# bitchess.net
KiCad netlist of a schematic drawn in EAGLE
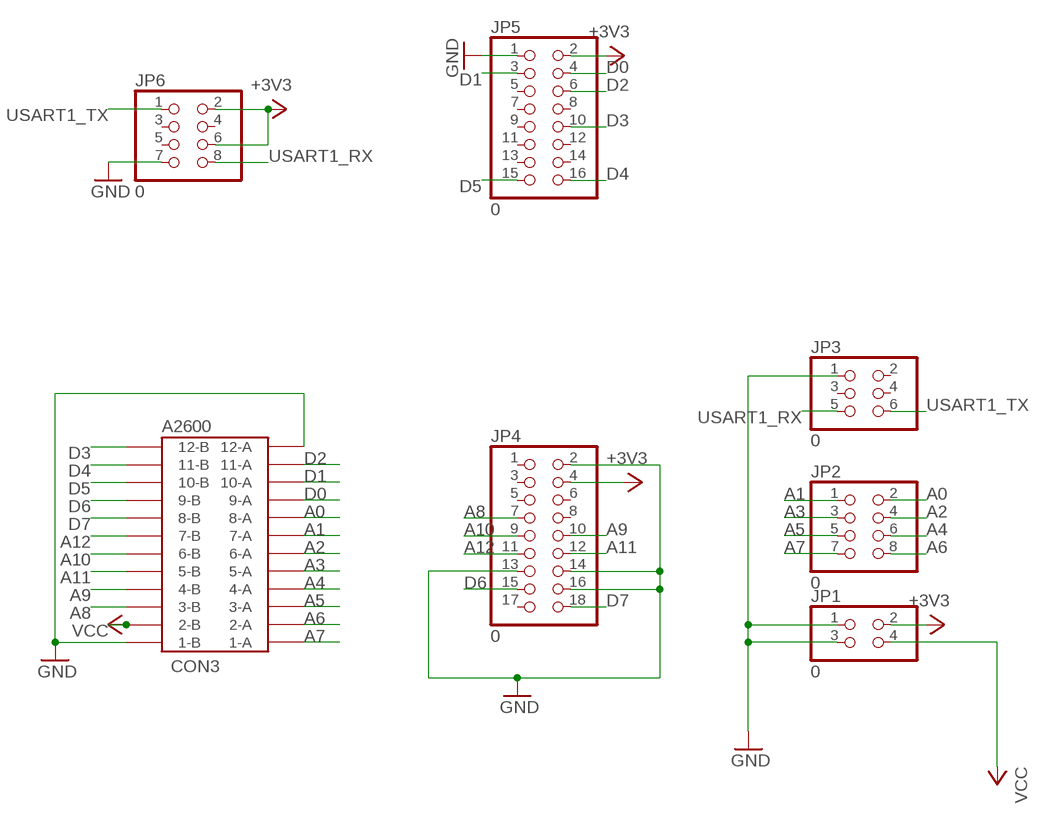
[diagram p0: schematic, sheet 1]

(export (version "E")
  (design (tool "Eeschema 10.0.6"))
  (components
    (comp (ref "CON3")
      (value "A2600")
      (footprint "eagle-import:24PINEDGE-254MM")
      (libsource (lib "eagle-import") (part "24PINEDGE-254MM"))
    )
    (comp (ref "JP1")
      (value "0")
      (footprint "eagle-import:2X02")
      (libsource (lib "eagle-import") (part "PINHD-2X2"))
    )
    (comp (ref "JP2")
      (value "0")
      (footprint "eagle-import:2X04")
      (libsource (lib "eagle-import") (part "PINHD-2X4"))
    )
    (comp (ref "JP3")
      (value "0")
      (footprint "eagle-import:2X03")
      (libsource (lib "eagle-import") (part "PINHD-2X3"))
    )
    (comp (ref "JP4")
      (value "0")
      (footprint "eagle-import:2X09")
      (libsource (lib "eagle-import") (part "PINHD-2X9"))
    )
    (comp (ref "JP5")
      (value "0")
      (footprint "eagle-import:2X08")
      (libsource (lib "eagle-import") (part "PINHD-2X8"))
    )
    (comp (ref "JP6")
      (value "0")
      (footprint "eagle-import:2X04")
      (libsource (lib "eagle-import") (part "PINHD-2X4"))
    )
  )
  (nets
    (net (code "1") (name "+3V3") (class "Default")
      (node (ref "JP1") (pin "2") (pinfunction "2_2") (pintype "passive"))
      (node (ref "JP4") (pin "4") (pinfunction "4_4") (pintype "passive"))
      (node (ref "JP5") (pin "2") (pinfunction "2_2") (pintype "passive"))
      (node (ref "JP6") (pin "2") (pinfunction "2_2") (pintype "passive"))
      (node (ref "JP6") (pin "6") (pinfunction "6_6") (pintype "passive"))
    )
    (net (code "2") (name "/A0") (class "Default")
      (node (ref "CON3") (pin "8-A") (pinfunction "8-A_8-A") (pintype "passive"))
      (node (ref "JP2") (pin "2") (pinfunction "2_2") (pintype "passive"))
    )
    (net (code "3") (name "/A1") (class "Default")
      (node (ref "CON3") (pin "7-A") (pinfunction "7-A_7-A") (pintype "passive"))
      (node (ref "JP2") (pin "1") (pinfunction "1_1") (pintype "passive"))
    )
    (net (code "4") (name "/A2") (class "Default")
      (node (ref "CON3") (pin "6-A") (pinfunction "6-A_6-A") (pintype "passive"))
      (node (ref "JP2") (pin "4") (pinfunction "4_4") (pintype "passive"))
    )
    (net (code "5") (name "/A3") (class "Default")
      (node (ref "CON3") (pin "5-A") (pinfunction "5-A_5-A") (pintype "passive"))
      (node (ref "JP2") (pin "3") (pinfunction "3_3") (pintype "passive"))
    )
    (net (code "6") (name "/A4") (class "Default")
      (node (ref "CON3") (pin "4-A") (pinfunction "4-A_4-A") (pintype "passive"))
      (node (ref "JP2") (pin "6") (pinfunction "6_6") (pintype "passive"))
    )
    (net (code "7") (name "/A5") (class "Default")
      (node (ref "CON3") (pin "3-A") (pinfunction "3-A_3-A") (pintype "passive"))
      (node (ref "JP2") (pin "5") (pinfunction "5_5") (pintype "passive"))
    )
    (net (code "8") (name "/A6") (class "Default")
      (node (ref "CON3") (pin "2-A") (pinfunction "2-A_2-A") (pintype "passive"))
      (node (ref "JP2") (pin "8") (pinfunction "8_8") (pintype "passive"))
    )
    (net (code "9") (name "/A7") (class "Default")
      (node (ref "CON3") (pin "1-A") (pinfunction "1-A_1-A") (pintype "passive"))
      (node (ref "JP2") (pin "7") (pinfunction "7_7") (pintype "passive"))
    )
    (net (code "10") (name "/A8") (class "Default")
      (node (ref "CON3") (pin "3-B") (pinfunction "3-B_3-B") (pintype "passive"))
      (node (ref "JP4") (pin "7") (pinfunction "7_7") (pintype "passive"))
    )
    (net (code "11") (name "/A9") (class "Default")
      (node (ref "CON3") (pin "4-B") (pinfunction "4-B_4-B") (pintype "passive"))
      (node (ref "JP4") (pin "10") (pinfunction "10_10") (pintype "passive"))
    )
    (net (code "12") (name "/A10") (class "Default")
      (node (ref "CON3") (pin "6-B") (pinfunction "6-B_6-B") (pintype "passive"))
      (node (ref "JP4") (pin "9") (pinfunction "9_9") (pintype "passive"))
    )
    (net (code "13") (name "/A11") (class "Default")
      (node (ref "CON3") (pin "5-B") (pinfunction "5-B_5-B") (pintype "passive"))
      (node (ref "JP4") (pin "12") (pinfunction "12_12") (pintype "passive"))
    )
    (net (code "14") (name "/A12") (class "Default")
      (node (ref "CON3") (pin "7-B") (pinfunction "7-B_7-B") (pintype "passive"))
      (node (ref "JP4") (pin "11") (pinfunction "11_11") (pintype "passive"))
    )
    (net (code "15") (name "/D0") (class "Default")
      (node (ref "CON3") (pin "9-A") (pinfunction "9-A_9-A") (pintype "passive"))
      (node (ref "JP5") (pin "4") (pinfunction "4_4") (pintype "passive"))
    )
    (net (code "16") (name "/D1") (class "Default")
      (node (ref "CON3") (pin "10-A") (pinfunction "10-A_10-A") (pintype "passive"))
      (node (ref "JP5") (pin "3") (pinfunction "3_3") (pintype "passive"))
    )
    (net (code "17") (name "/D2") (class "Default")
      (node (ref "CON3") (pin "11-A") (pinfunction "11-A_11-A") (pintype "passive"))
      (node (ref "JP5") (pin "6") (pinfunction "6_6") (pintype "passive"))
    )
    (net (code "18") (name "/D3") (class "Default")
      (node (ref "CON3") (pin "12-B") (pinfunction "12-B_12-B") (pintype "passive"))
      (node (ref "JP5") (pin "10") (pinfunction "10_10") (pintype "passive"))
    )
    (net (code "19") (name "/D4") (class "Default")
      (node (ref "CON3") (pin "11-B") (pinfunction "11-B_11-B") (pintype "passive"))
      (node (ref "JP5") (pin "16") (pinfunction "16_16") (pintype "passive"))
    )
    (net (code "20") (name "/D5") (class "Default")
      (node (ref "CON3") (pin "10-B") (pinfunction "10-B_10-B") (pintype "passive"))
      (node (ref "JP5") (pin "15") (pinfunction "15_15") (pintype "passive"))
    )
    (net (code "21") (name "/D6") (class "Default")
      (node (ref "CON3") (pin "9-B") (pinfunction "9-B_9-B") (pintype "passive"))
      (node (ref "JP4") (pin "15") (pinfunction "15_15") (pintype "passive"))
    )
    (net (code "22") (name "/D7") (class "Default")
      (node (ref "CON3") (pin "8-B") (pinfunction "8-B_8-B") (pintype "passive"))
      (node (ref "JP4") (pin "18") (pinfunction "18_18") (pintype "passive"))
    )
    (net (code "23") (name "/USART1_RX") (class "Default")
      (node (ref "JP3") (pin "5") (pinfunction "5_5") (pintype "passive"))
      (node (ref "JP6") (pin "8") (pinfunction "8_8") (pintype "passive"))
    )
    (net (code "24") (name "/USART1_TX") (class "Default")
      (node (ref "JP3") (pin "6") (pinfunction "6_6") (pintype "passive"))
      (node (ref "JP6") (pin "1") (pinfunction "1_1") (pintype "passive"))
    )
    (net (code "25") (name "GND") (class "Default")
      (node (ref "CON3") (pin "1-B") (pinfunction "1-B_1-B") (pintype "passive"))
      (node (ref "CON3") (pin "12-A") (pinfunction "12-A_12-A") (pintype "passive"))
      (node (ref "JP1") (pin "1") (pinfunction "1_1") (pintype "passive"))
      (node (ref "JP1") (pin "3") (pinfunction "3_3") (pintype "passive"))
      (node (ref "JP3") (pin "1") (pinfunction "1_1") (pintype "passive"))
      (node (ref "JP4") (pin "13") (pinfunction "13_13") (pintype "passive"))
      (node (ref "JP4") (pin "14") (pinfunction "14_14") (pintype "passive"))
      (node (ref "JP4") (pin "16") (pinfunction "16_16") (pintype "passive"))
      (node (ref "JP4") (pin "2") (pinfunction "2_2") (pintype "passive"))
      (node (ref "JP5") (pin "1") (pinfunction "1_1") (pintype "passive"))
      (node (ref "JP6") (pin "7") (pinfunction "7_7") (pintype "passive"))
    )
    (net (code "26") (name "VCC") (class "Default")
      (node (ref "CON3") (pin "2-B") (pinfunction "2-B_2-B") (pintype "passive"))
      (node (ref "JP1") (pin "4") (pinfunction "4_4") (pintype "passive"))
    )
    (net (code "27") (name "unconnected-(JP3-Pad2)") (class "Default")
      (node (ref "JP3") (pin "2") (pinfunction "2_2") (pintype "passive"))
    )
    (net (code "28") (name "unconnected-(JP3-Pad3)") (class "Default")
      (node (ref "JP3") (pin "3") (pinfunction "3_3") (pintype "passive"))
    )
    (net (code "29") (name "unconnected-(JP3-Pad4)") (class "Default")
      (node (ref "JP3") (pin "4") (pinfunction "4_4") (pintype "passive"))
    )
    (net (code "30") (name "unconnected-(JP4-Pad1)") (class "Default")
      (node (ref "JP4") (pin "1") (pinfunction "1_1") (pintype "passive"))
    )
    (net (code "31") (name "unconnected-(JP4-Pad3)") (class "Default")
      (node (ref "JP4") (pin "3") (pinfunction "3_3") (pintype "passive"))
    )
    (net (code "32") (name "unconnected-(JP4-Pad5)") (class "Default")
      (node (ref "JP4") (pin "5") (pinfunction "5_5") (pintype "passive"))
    )
    (net (code "33") (name "unconnected-(JP4-Pad6)") (class "Default")
      (node (ref "JP4") (pin "6") (pinfunction "6_6") (pintype "passive"))
    )
    (net (code "34") (name "unconnected-(JP4-Pad8)") (class "Default")
      (node (ref "JP4") (pin "8") (pinfunction "8_8") (pintype "passive"))
    )
    (net (code "35") (name "unconnected-(JP4-Pad17)") (class "Default")
      (node (ref "JP4") (pin "17") (pinfunction "17_17") (pintype "passive"))
    )
    (net (code "36") (name "unconnected-(JP5-Pad5)") (class "Default")
      (node (ref "JP5") (pin "5") (pinfunction "5_5") (pintype "passive"))
    )
    (net (code "37") (name "unconnected-(JP5-Pad7)") (class "Default")
      (node (ref "JP5") (pin "7") (pinfunction "7_7") (pintype "passive"))
    )
    (net (code "38") (name "unconnected-(JP5-Pad8)") (class "Default")
      (node (ref "JP5") (pin "8") (pinfunction "8_8") (pintype "passive"))
    )
    (net (code "39") (name "unconnected-(JP5-Pad9)") (class "Default")
      (node (ref "JP5") (pin "9") (pinfunction "9_9") (pintype "passive"))
    )
    (net (code "40") (name "unconnected-(JP5-Pad11)") (class "Default")
      (node (ref "JP5") (pin "11") (pinfunction "11_11") (pintype "passive"))
    )
    (net (code "41") (name "unconnected-(JP5-Pad12)") (class "Default")
      (node (ref "JP5") (pin "12") (pinfunction "12_12") (pintype "passive"))
    )
    (net (code "42") (name "unconnected-(JP5-Pad13)") (class "Default")
      (node (ref "JP5") (pin "13") (pinfunction "13_13") (pintype "passive"))
    )
    (net (code "43") (name "unconnected-(JP5-Pad14)") (class "Default")
      (node (ref "JP5") (pin "14") (pinfunction "14_14") (pintype "passive"))
    )
    (net (code "44") (name "unconnected-(JP6-Pad3)") (class "Default")
      (node (ref "JP6") (pin "3") (pinfunction "3_3") (pintype "passive"))
    )
    (net (code "45") (name "unconnected-(JP6-Pad4)") (class "Default")
      (node (ref "JP6") (pin "4") (pinfunction "4_4") (pintype "passive"))
    )
    (net (code "46") (name "unconnected-(JP6-Pad5)") (class "Default")
      (node (ref "JP6") (pin "5") (pinfunction "5_5") (pintype "passive"))
    )
  )
)
